# Client_Node_1.net
KiCad netlist of a schematic drawn in Altium Designer
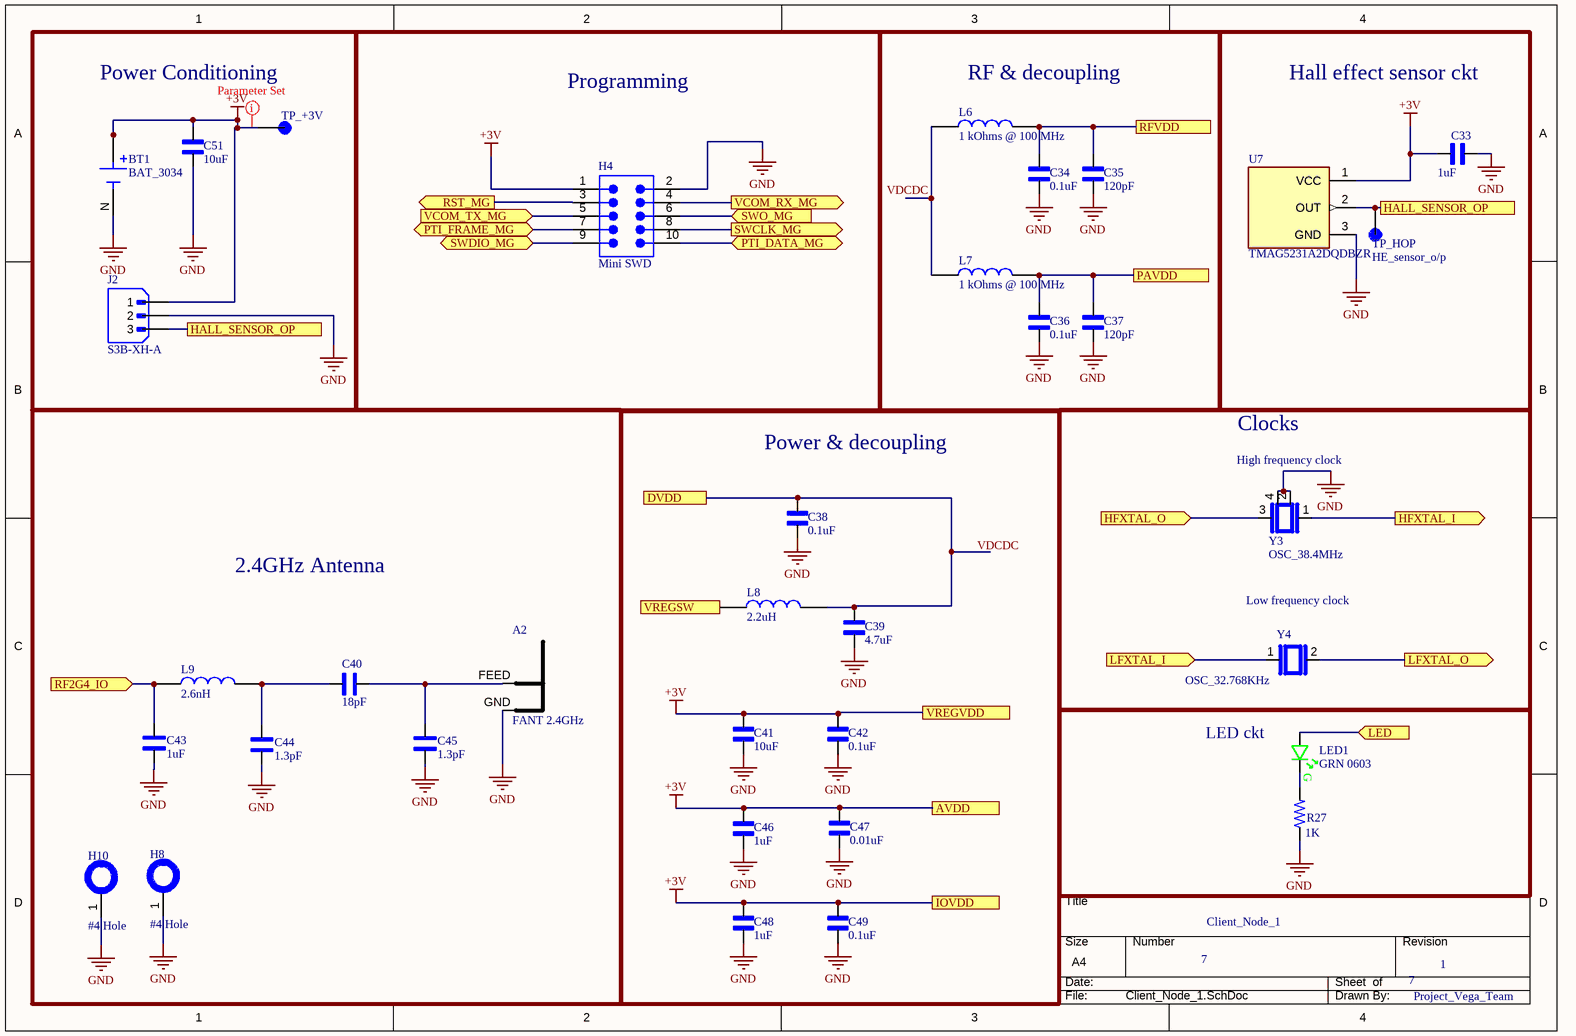
[diagram p0: Client_Node_1.SchDoc]

(export (version "E")
  (design (tool "Eeschema 10.0.6"))
  (components
    (comp (ref "A2")
      (value "FANT 2.4GHz")
      (footprint "FANT_2P4")
      (description "Inverted F antenna")
      (libsource (lib "Project_Vega") (part "FANT_2P4"))
    )
    (comp (ref "BT1")
      (value "BAT_3034")
      (footprint "BAT_3034")
      (description "SMT Holder for 20mm Cell-Tin Nickel Plate")
      (fields (field (name "MP") "3034") (field (name "MF") "Keystone Electronics Corp."))
      (libsource (lib "Project_Vega") (part "BAT_3034"))
    )
    (comp (ref "C33")
      (value "1uF")
      (footprint "CAPC1608X90")
      (description "0.1 ÂµF Â±10% 50V Ceramic Capacitor X7R 0603 (1608 Metric)")
      (fields (field (name "MF") "Yageo") (field (name "MP") "CC0603KRX7R9BB104"))
      (libsource (lib "") (part "CC0603KRX7R9BB104_1"))
    )
    (comp (ref "C34")
      (value "0.1uF")
      (footprint "CAPC1608X90")
      (description "0.1 ÂµF Â±10% 50V Ceramic Capacitor X7R 0603 (1608 Metric)")
      (fields (field (name "MF") "Yageo") (field (name "MP") "CC0603KRX7R9BB104"))
      (libsource (lib "Project_Vega") (part "CC0603KRX7R9BB104"))
    )
    (comp (ref "C35")
      (value "120pF")
      (footprint "CAPC1608X90")
      (description "0.1 ÂµF Â±10% 50V Ceramic Capacitor X7R 0603 (1608 Metric)")
      (fields (field (name "MF") "Yageo") (field (name "MP") "CC0603KRX7R9BB104"))
      (libsource (lib "Project_Vega") (part "CC0603KRX7R9BB104"))
    )
    (comp (ref "C36")
      (value "0.1uF")
      (footprint "CAPC1608X90")
      (description "0.1 ÂµF Â±10% 50V Ceramic Capacitor X7R 0603 (1608 Metric)")
      (fields (field (name "MF") "Yageo") (field (name "MP") "CC0603KRX7R9BB104"))
      (libsource (lib "Project_Vega") (part "CC0603KRX7R9BB104"))
    )
    (comp (ref "C37")
      (value "120pF")
      (footprint "CAPC1608X90")
      (description "0.1 ÂµF Â±10% 50V Ceramic Capacitor X7R 0603 (1608 Metric)")
      (fields (field (name "MF") "Yageo") (field (name "MP") "CC0603KRX7R9BB104"))
      (libsource (lib "Project_Vega") (part "CC0603KRX7R9BB104"))
    )
    (comp (ref "C38")
      (value "0.1uF")
      (footprint "CAPC1608X90")
      (description "0.1 ÂµF Â±10% 50V Ceramic Capacitor X7R 0603 (1608 Metric)")
      (fields (field (name "MF") "Yageo") (field (name "MP") "CC0603KRX7R9BB104"))
      (libsource (lib "Project_Vega") (part "CC0603KRX7R9BB104"))
    )
    (comp (ref "C39")
      (value "4.7uF")
      (footprint "CAPC1608X90")
      (description "0.1 ÂµF Â±10% 50V Ceramic Capacitor X7R 0603 (1608 Metric)")
      (fields (field (name "MF") "Yageo") (field (name "MP") "CC0603KRX7R9BB104"))
      (libsource (lib "Project_Vega") (part "CC0603KRX7R9BB104"))
    )
    (comp (ref "C40")
      (value "18pF")
      (footprint "0402_Passive_Capacitor")
      (description "MULTILAYER CERAMIC CAPACITORS MLCC - SMD/SMT 1UF 25V 0402 ROHS")
      (fields (field (name "MFR PART #") "CL05A105KA5NQNC") (field (name "LCSC PART#") "C52923"))
      (libsource (lib "Project_Vega") (part "C_0402"))
    )
    (comp (ref "C41")
      (value "10uF")
      (footprint "CAPC1608X90")
      (description "0.1 ÂµF Â±10% 50V Ceramic Capacitor X7R 0603 (1608 Metric)")
      (fields (field (name "MF") "Yageo") (field (name "MP") "CC0603KRX7R9BB104"))
      (libsource (lib "Project_Vega") (part "CC0603KRX7R9BB104"))
    )
    (comp (ref "C42")
      (value "0.1uF")
      (footprint "CAPC1608X90")
      (description "0.1 ÂµF Â±10% 50V Ceramic Capacitor X7R 0603 (1608 Metric)")
      (fields (field (name "MF") "Yageo") (field (name "MP") "CC0603KRX7R9BB104"))
      (libsource (lib "Project_Vega") (part "CC0603KRX7R9BB104"))
    )
    (comp (ref "C43")
      (value "1uF")
      (footprint "0402_Passive_Capacitor")
      (description "MULTILAYER CERAMIC CAPACITORS MLCC - SMD/SMT 1UF 25V 0402 ROHS")
      (fields (field (name "MFR PART #") "CL05A105KA5NQNC") (field (name "LCSC PART#") "C52923"))
      (libsource (lib "Project_Vega") (part "C_0402"))
    )
    (comp (ref "C44")
      (value "1.3pF")
      (footprint "0402_Passive_Capacitor")
      (description "MULTILAYER CERAMIC CAPACITORS MLCC - SMD/SMT 1UF 25V 0402 ROHS")
      (fields (field (name "MFR PART #") "CL05A105KA5NQNC") (field (name "LCSC PART#") "C52923"))
      (libsource (lib "Project_Vega") (part "C_0402"))
    )
    (comp (ref "C45")
      (value "1.3pF")
      (footprint "0402_Passive_Capacitor")
      (description "MULTILAYER CERAMIC CAPACITORS MLCC - SMD/SMT 1UF 25V 0402 ROHS")
      (fields (field (name "MFR PART #") "CL05A105KA5NQNC") (field (name "LCSC PART#") "C52923"))
      (libsource (lib "Project_Vega") (part "C_0402"))
    )
    (comp (ref "C46")
      (value "1uF")
      (footprint "CAPC1608X90")
      (description "0.1 ÂµF Â±10% 50V Ceramic Capacitor X7R 0603 (1608 Metric)")
      (fields (field (name "MF") "Yageo") (field (name "MP") "CC0603KRX7R9BB104"))
      (libsource (lib "Project_Vega") (part "CC0603KRX7R9BB104"))
    )
    (comp (ref "C47")
      (value "0.01uF")
      (footprint "CAPC1608X90")
      (description "0.1 ÂµF Â±10% 50V Ceramic Capacitor X7R 0603 (1608 Metric)")
      (fields (field (name "MF") "Yageo") (field (name "MP") "CC0603KRX7R9BB104"))
      (libsource (lib "Project_Vega") (part "CC0603KRX7R9BB104"))
    )
    (comp (ref "C48")
      (value "1uF")
      (footprint "CAPC1608X90")
      (description "0.1 ÂµF Â±10% 50V Ceramic Capacitor X7R 0603 (1608 Metric)")
      (fields (field (name "MF") "Yageo") (field (name "MP") "CC0603KRX7R9BB104"))
      (libsource (lib "Project_Vega") (part "CC0603KRX7R9BB104"))
    )
    (comp (ref "C49")
      (value "0.1uF")
      (footprint "CAPC1608X90")
      (description "0.1 ÂµF Â±10% 50V Ceramic Capacitor X7R 0603 (1608 Metric)")
      (fields (field (name "MF") "Yageo") (field (name "MP") "CC0603KRX7R9BB104"))
      (libsource (lib "Project_Vega") (part "CC0603KRX7R9BB104"))
    )
    (comp (ref "C51")
      (value "10uF")
      (footprint "CAPC1608X90")
      (description "0.1 ÂµF Â±10% 50V Ceramic Capacitor X7R 0603 (1608 Metric)")
      (fields (field (name "MF") "Yageo") (field (name "MP") "CC0603KRX7R9BB104"))
      (libsource (lib "Project_Vega") (part "CC0603KRX7R9BB104"))
    )
    (comp (ref "H4")
      (value "Mini SWD")
      (footprint "FTSH-105-01-XXX-DV-K")
      (description "Mini SWD 0.05 Pitch Connector - 10 Pin SMT Box Header ¦ Adafruit Industries 4048")
      (fields
        (field (name "MANUFACTURER") "Adafruit Industries")
        (field (name "MANUFACTURER PART NUMBER") "4048")
      )
      (libsource (lib "Project_Vega") (part "Debug Connector Mini SWD - 0.05{dblquote}"))
    )
    (comp (ref "H8")
      (value "#4 Hole")
      (footprint "HOLE_#4")
      (libsource (lib "Project_Vega") (part "HOLE_#4"))
    )
    (comp (ref "H10")
      (value "#4 Hole")
      (footprint "HOLE_#4")
      (libsource (lib "Project_Vega") (part "HOLE_#4"))
    )
    (comp (ref "J2")
      (value "S3B-XH-A")
      (footprint "JST_S3B-XH-A")
      (description "Connector Header Through Hole 3 position 0.098 (2.50mm)")
      (fields (field (name "MF") "JST Sales") (field (name "MP") "B3B-XH-A(LF)(SN)"))
      (libsource (lib "Project_Vega") (part "S3B-XH-A"))
    )
    (comp (ref "L6")
      (value "1 kOhms @ 100 MHz")
      (footprint "INDC1608X95N")
      (description "Inductor with Inductance 10uH Tol.+/-20% Package 0603 (1608)")
      (fields (field (name "MP") "LQM18DN100M70L") (field (name "MF") "Murata Electronics"))
      (libsource (lib "Project_Vega") (part "LQM18DN100M70L"))
    )
    (comp (ref "L7")
      (value "1 kOhms @ 100 MHz")
      (footprint "INDC1608X95N")
      (description "Inductor with Inductance 10uH Tol.+/-20% Package 0603 (1608)")
      (fields (field (name "MP") "LQM18DN100M70L") (field (name "MF") "Murata Electronics"))
      (libsource (lib "Project_Vega") (part "LQM18DN100M70L"))
    )
    (comp (ref "L8")
      (value "2.2uH")
      (footprint "INDC1608X95N")
      (description "Inductor with Inductance 10uH Tol.+/-20% Package 0603 (1608)")
      (fields (field (name "MP") "LQM18DN100M70L") (field (name "MF") "Murata Electronics"))
      (libsource (lib "Project_Vega") (part "LQM18DN100M70L"))
    )
    (comp (ref "L9")
      (value "2.6nH")
      (footprint "0402_Inductor")
      (description "Inductor Package 0603")
      (fields (field (name "MP") "LQM18DN100M70L") (field (name "MF") "Murata Electronics"))
      (libsource (lib "Project_Vega") (part "IND_0402"))
    )
    (comp (ref "LED1")
      (value "GRN 0603")
      (footprint "LED_0603_GRN_WL-SMCW")
      (description "LED, 0603, GREEN, 430MCD, 520NM")
      (fields
        (field (name "MANUFACTURER") "Wurth Electronics")
        (field (name "MANUFACTURER PART NUMBER") "150060GS75000")
      )
      (libsource (lib "Project_Vega") (part "LED_green"))
    )
    (comp (ref "R27")
      (value "1K")
      (footprint "RES_0603")
      (description "Thick film general purpose resistor 0603")
      (fields (field (name "MP") "RC0603JR-070RL"))
      (libsource (lib "Project_Vega") (part "RES_0603"))
    )
    (comp (ref "TP_+3V")
      (value "+5V")
      (footprint "1")
      (description "SMT Test Point- Mininature-1000 pc Reels")
      (fields (field (name "MP") "5019") (field (name "MF") "Keystone Electronics"))
      (libsource (lib "Project_Vega") (part "Test_point"))
    )
    (comp (ref "TP_HOP")
      (value "HE_sensor_o/p")
      (footprint "1")
      (description "SMT Test Point- Mininature-1000 pc Reels")
      (fields (field (name "MP") "5019") (field (name "MF") "Keystone Electronics"))
      (libsource (lib "Project_Vega") (part "Test_point"))
    )
    (comp (ref "U7")
      (value "TMAG5231A2DQDBZR")
      (footprint "SOT95P237X112-3N")
      (description "Low-power, low-voltage (1.65 V to 5.5 V) Hall-effect switch 3-SOT-23 -40 to 125")
      (fields
        (field (name "MF") "{'manufacturer': u'Texas Instruments'}")
        (field (name "MANUFACTURER") "Texas Instruments")
      )
      (libsource (lib "Project_Vega") (part "TMAG5231A2DQDBZR"))
    )
    (comp (ref "Y3")
      (value "OSC_38.4MHz")
      (footprint "OSC_38.4MHz")
      (description "38.4 MHz ±10ppm Crystal 10pF 40 Ohms 4-SMD, No Lead")
      (fields
        (field (name "MF") "{'manufacturer': u'Murata Electronics'}")
        (field (name "MP") "XRCGB38M400F2P00R0")
      )
      (libsource (lib "Project_Vega") (part "OSC_38.4MHz"))
    )
    (comp (ref "Y4")
      (value "OSC_32.768KHz")
      (footprint "OSC_32.768KHz")
      (description "Tuning Fork Crystal 32.768kHz in 1.2 x 2.0mm package")
      (fields (field (name "MF") "Micro Crystal") (field (name "MP") "CM8V-T1A-32.768KHZ-7PF-20PPM-TA-QC"))
      (libsource (lib "Project_Vega") (part "OSC_32.768KHz"))
    )
  )
  (nets
    (net (code "1") (name "+3V") (class "Default")
      (node (ref "BT1") (pin "P1") (pinfunction "POS_P1") (pintype "passive"))
      (node (ref "BT1") (pin "P2") (pinfunction "POS_P2") (pintype "passive"))
      (node (ref "C33") (pin "2") (pinfunction "2_2") (pintype "passive"))
      (node (ref "C41") (pin "1") (pinfunction "1_1") (pintype "passive"))
      (node (ref "C42") (pin "1") (pinfunction "1_1") (pintype "passive"))
      (node (ref "C46") (pin "1") (pinfunction "1_1") (pintype "passive"))
      (node (ref "C47") (pin "1") (pinfunction "1_1") (pintype "passive"))
      (node (ref "C48") (pin "1") (pinfunction "1_1") (pintype "passive"))
      (node (ref "C49") (pin "1") (pinfunction "1_1") (pintype "passive"))
      (node (ref "C51") (pin "1") (pinfunction "1_1") (pintype "passive"))
      (node (ref "H4") (pin "1") (pinfunction "1_1") (pintype "passive"))
      (node (ref "J2") (pin "1") (pinfunction "1_1") (pintype "passive"))
      (node (ref "TP_+3V") (pin "TP") (pinfunction "1_TP") (pintype "passive"))
      (node (ref "U7") (pin "1") (pinfunction "VCC_1") (pintype "power_in"))
    )
    (net (code "2") (name "/DVDD") (class "Default")
      (node (ref "C38") (pin "1") (pinfunction "1_1") (pintype "passive"))
      (node (ref "C39") (pin "1") (pinfunction "1_1") (pintype "passive"))
      (node (ref "L8") (pin "2") (pinfunction "2_2") (pintype "passive"))
    )
    (net (code "3") (name "/HALL_SENSOR_OP") (class "Default")
      (node (ref "J2") (pin "3") (pinfunction "3_3") (pintype "passive"))
      (node (ref "TP_HOP") (pin "TP") (pinfunction "1_TP") (pintype "passive"))
      (node (ref "U7") (pin "2") (pinfunction "OUT_2") (pintype "output"))
    )
    (net (code "4") (name "/HFXTAL_I") (class "Default")
      (node (ref "Y3") (pin "1") (pinfunction "1_1") (pintype "passive"))
    )
    (net (code "5") (name "/HFXTAL_O") (class "Default")
      (node (ref "Y3") (pin "3") (pinfunction "3_3") (pintype "passive"))
    )
    (net (code "6") (name "/LED") (class "Default")
      (node (ref "LED1") (pin "A") (pinfunction "A_A") (pintype "passive"))
    )
    (net (code "7") (name "/LFXTAL_I") (class "Default")
      (node (ref "Y4") (pin "1") (pinfunction "1_1") (pintype "passive"))
    )
    (net (code "8") (name "/LFXTAL_O") (class "Default")
      (node (ref "Y4") (pin "2") (pinfunction "2_2") (pintype "passive"))
    )
    (net (code "9") (name "/PAVDD") (class "Default")
      (node (ref "C36") (pin "1") (pinfunction "1_1") (pintype "passive"))
      (node (ref "C37") (pin "1") (pinfunction "1_1") (pintype "passive"))
      (node (ref "L7") (pin "2") (pinfunction "2_2") (pintype "passive"))
    )
    (net (code "10") (name "/PTI_DATA_MG") (class "Default")
      (node (ref "H4") (pin "10") (pinfunction "10_10") (pintype "passive"))
    )
    (net (code "11") (name "/PTI_FRAME_MG") (class "Default")
      (node (ref "H4") (pin "7") (pinfunction "7_7") (pintype "passive"))
    )
    (net (code "12") (name "/RF2G4_IO") (class "Default")
      (node (ref "C43") (pin "2") (pinfunction "2_2") (pintype "passive"))
      (node (ref "L9") (pin "1") (pinfunction "1_1") (pintype "passive"))
    )
    (net (code "13") (name "/RFVDD") (class "Default")
      (node (ref "C34") (pin "1") (pinfunction "1_1") (pintype "passive"))
      (node (ref "C35") (pin "1") (pinfunction "1_1") (pintype "passive"))
      (node (ref "L6") (pin "2") (pinfunction "2_2") (pintype "passive"))
    )
    (net (code "14") (name "/RST_MG") (class "Default")
      (node (ref "H4") (pin "3") (pinfunction "3_3") (pintype "passive"))
    )
    (net (code "15") (name "/SWCLK_MG") (class "Default")
      (node (ref "H4") (pin "8") (pinfunction "8_8") (pintype "passive"))
    )
    (net (code "16") (name "/SWDIO_MG") (class "Default")
      (node (ref "H4") (pin "9") (pinfunction "9_9") (pintype "passive"))
    )
    (net (code "17") (name "/SWO_MG") (class "Default")
      (node (ref "H4") (pin "6") (pinfunction "6_6") (pintype "passive"))
    )
    (net (code "18") (name "/VCOM_RX_MG") (class "Default")
      (node (ref "H4") (pin "4") (pinfunction "4_4") (pintype "passive"))
    )
    (net (code "19") (name "/VCOM_TX_MG") (class "Default")
      (node (ref "H4") (pin "5") (pinfunction "5_5") (pintype "passive"))
    )
    (net (code "20") (name "/VDCDC") (class "Default")
      (node (ref "L6") (pin "1") (pinfunction "1_1") (pintype "passive"))
      (node (ref "L7") (pin "1") (pinfunction "1_1") (pintype "passive"))
    )
    (net (code "21") (name "/VREGSW") (class "Default")
      (node (ref "L8") (pin "1") (pinfunction "1_1") (pintype "passive"))
    )
    (net (code "22") (name "GND") (class "Default")
      (node (ref "A2") (pin "GND") (pinfunction "6_GND") (pintype "passive"))
      (node (ref "BT1") (pin "N") (pinfunction "NEG_N") (pintype "passive"))
      (node (ref "C33") (pin "1") (pinfunction "1_1") (pintype "passive"))
      (node (ref "C34") (pin "2") (pinfunction "2_2") (pintype "passive"))
      (node (ref "C35") (pin "2") (pinfunction "2_2") (pintype "passive"))
      (node (ref "C36") (pin "2") (pinfunction "2_2") (pintype "passive"))
      (node (ref "C37") (pin "2") (pinfunction "2_2") (pintype "passive"))
      (node (ref "C38") (pin "2") (pinfunction "2_2") (pintype "passive"))
      (node (ref "C39") (pin "2") (pinfunction "2_2") (pintype "passive"))
      (node (ref "C41") (pin "2") (pinfunction "2_2") (pintype "passive"))
      (node (ref "C42") (pin "2") (pinfunction "2_2") (pintype "passive"))
      (node (ref "C43") (pin "1") (pinfunction "1_1") (pintype "passive"))
      (node (ref "C44") (pin "1") (pinfunction "1_1") (pintype "passive"))
      (node (ref "C45") (pin "2") (pinfunction "2_2") (pintype "passive"))
      (node (ref "C46") (pin "2") (pinfunction "2_2") (pintype "passive"))
      (node (ref "C47") (pin "2") (pinfunction "2_2") (pintype "passive"))
      (node (ref "C48") (pin "2") (pinfunction "2_2") (pintype "passive"))
      (node (ref "C49") (pin "2") (pinfunction "2_2") (pintype "passive"))
      (node (ref "C51") (pin "2") (pinfunction "2_2") (pintype "passive"))
      (node (ref "H10") (pin "1") (pinfunction "1_1") (pintype "passive"))
      (node (ref "H4") (pin "2") (pinfunction "2_2") (pintype "passive"))
      (node (ref "H8") (pin "1") (pinfunction "1_1") (pintype "passive"))
      (node (ref "J2") (pin "2") (pinfunction "2_2") (pintype "passive"))
      (node (ref "R27") (pin "1") (pinfunction "1_1") (pintype "passive"))
      (node (ref "U7") (pin "3") (pinfunction "GND_3") (pintype "power_in"))
      (node (ref "Y3") (pin "2") (pinfunction "2_2") (pintype "passive"))
      (node (ref "Y3") (pin "4") (pinfunction "4_4") (pintype "passive"))
    )
    (net (code "23") (name "Net-(A2-6-PadFEED)") (class "Default")
      (node (ref "A2") (pin "FEED") (pinfunction "6_FEED") (pintype "passive"))
      (node (ref "C40") (pin "2") (pinfunction "2_2") (pintype "passive"))
      (node (ref "C45") (pin "1") (pinfunction "1_1") (pintype "passive"))
    )
    (net (code "24") (name "Net-(C40-Pad1)") (class "Default")
      (node (ref "C40") (pin "1") (pinfunction "1_1") (pintype "passive"))
      (node (ref "C44") (pin "2") (pinfunction "2_2") (pintype "passive"))
      (node (ref "L9") (pin "2") (pinfunction "2_2") (pintype "passive"))
    )
    (net (code "25") (name "Net-(LED1-PadC)") (class "Default")
      (node (ref "LED1") (pin "C") (pinfunction "C_C") (pintype "passive"))
      (node (ref "R27") (pin "2") (pinfunction "2_2") (pintype "passive"))
    )
  )
)
